# Front_right_lamp_v2.net
KiCad netlist of a schematic drawn in EAGLE
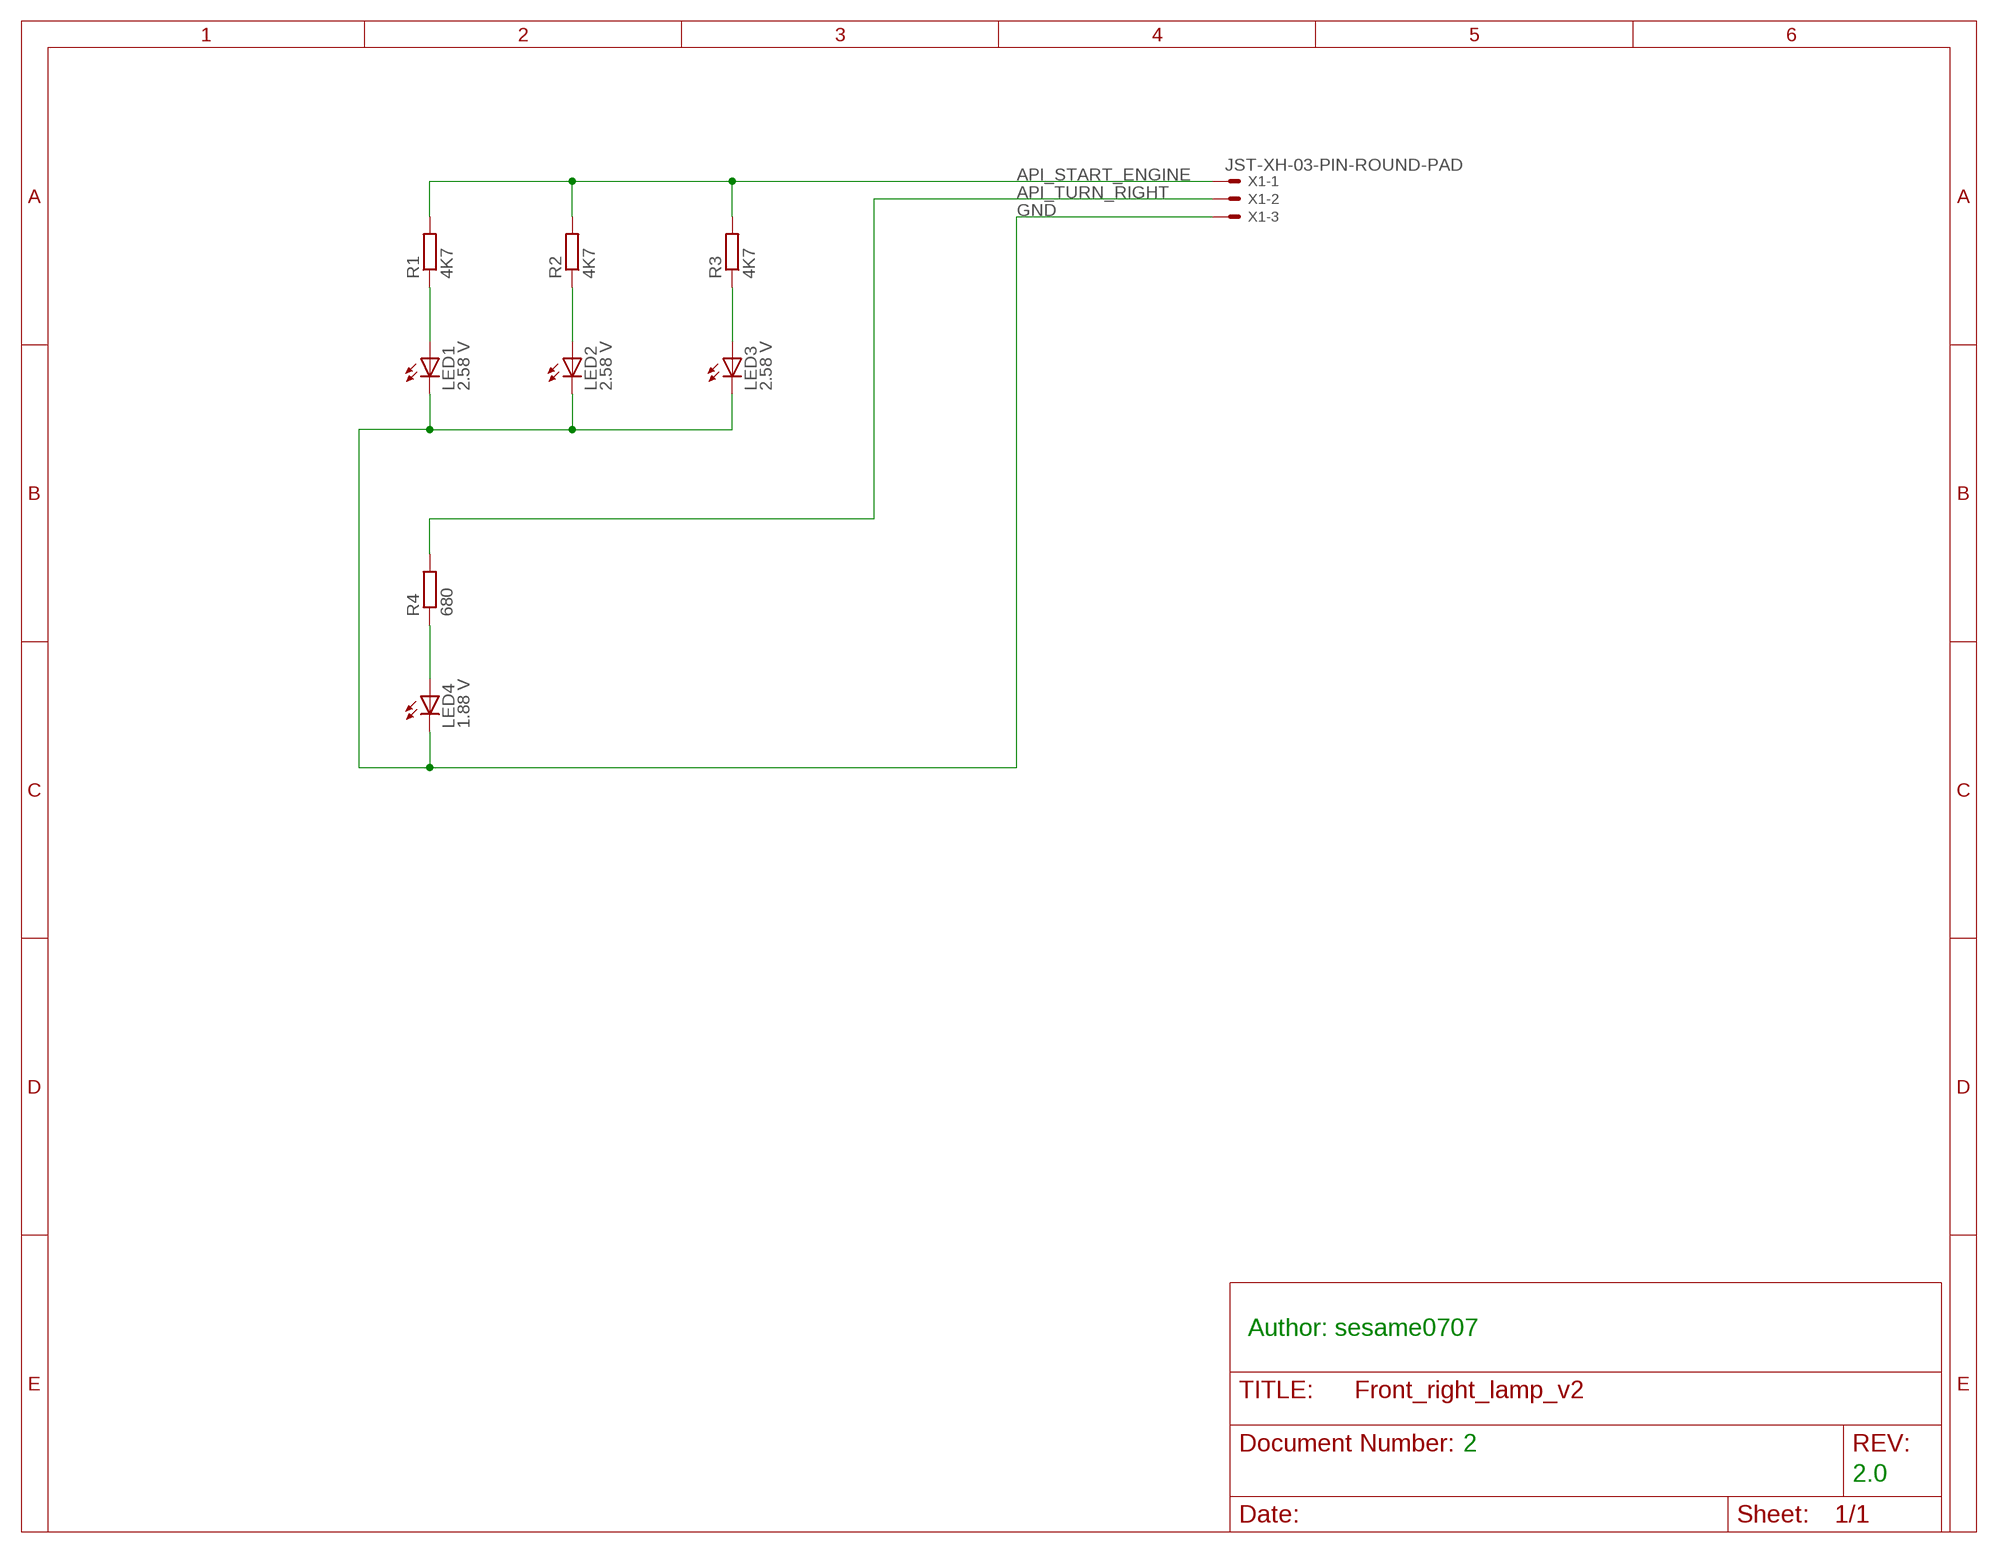
[diagram p0: schematic, sheet 1]

(export (version "E")
  (design (tool "Eeschema 10.0.6"))
  (components
    (comp (ref "LED1")
      (value "2.58 V")
      (footprint "eagle-import:LED5MM")
      (libsource (lib "eagle-import") (part "LED5MM"))
    )
    (comp (ref "LED2")
      (value "2.58 V")
      (footprint "eagle-import:LED5MM")
      (libsource (lib "eagle-import") (part "LED5MM"))
    )
    (comp (ref "LED3")
      (value "2.58 V")
      (footprint "eagle-import:LED5MM")
      (libsource (lib "eagle-import") (part "LED5MM"))
    )
    (comp (ref "LED4")
      (value "1.88 V")
      (footprint "eagle-import:LED5MM")
      (libsource (lib "eagle-import") (part "LED5MM"))
    )
    (comp (ref "R1")
      (value "4K7")
      (footprint "eagle-import:0204V")
      (libsource (lib "eagle-import") (part "R-EU_0204/2V"))
    )
    (comp (ref "R2")
      (value "4K7")
      (footprint "eagle-import:0204V")
      (libsource (lib "eagle-import") (part "R-EU_0204/2V"))
    )
    (comp (ref "R3")
      (value "4K7")
      (footprint "eagle-import:0204V")
      (libsource (lib "eagle-import") (part "R-EU_0204/2V"))
    )
    (comp (ref "R4")
      (value "680")
      (footprint "eagle-import:0204V")
      (libsource (lib "eagle-import") (part "R-EU_0204/2V"))
    )
    (comp (ref "X1")
      (value "JST-XH-03-PIN-ROUND-PAD")
      (footprint "eagle-import:JST-XH-03-PACKAGE-ROUND-PAD")
      (libsource (lib "eagle-import") (part "JST-XH-03-PIN-ROUND-PAD"))
    )
  )
  (nets
    (net (code "1") (name "/API_START_ENGINE") (class "Default")
      (node (ref "R1") (pin "2") (pinfunction "2_2") (pintype "passive"))
      (node (ref "R2") (pin "2") (pinfunction "2_2") (pintype "passive"))
      (node (ref "R3") (pin "2") (pinfunction "2_2") (pintype "passive"))
      (node (ref "X1") (pin "1") (pinfunction "S_1") (pintype "passive"))
    )
    (net (code "2") (name "/API_TURN_RIGHT") (class "Default")
      (node (ref "R4") (pin "2") (pinfunction "2_2") (pintype "passive"))
      (node (ref "X1") (pin "2") (pinfunction "S_2") (pintype "passive"))
    )
    (net (code "3") (name "/GND") (class "Default")
      (node (ref "LED1") (pin "K") (pinfunction "C_K") (pintype "passive"))
      (node (ref "LED2") (pin "K") (pinfunction "C_K") (pintype "passive"))
      (node (ref "LED3") (pin "K") (pinfunction "C_K") (pintype "passive"))
      (node (ref "LED4") (pin "K") (pinfunction "C_K") (pintype "passive"))
      (node (ref "X1") (pin "3") (pinfunction "S_3") (pintype "passive"))
    )
    (net (code "4") (name "Net-(LED1-PadA)") (class "Default")
      (node (ref "LED1") (pin "A") (pinfunction "A_A") (pintype "passive"))
      (node (ref "R1") (pin "1") (pinfunction "1_1") (pintype "passive"))
    )
    (net (code "5") (name "Net-(LED2-PadA)") (class "Default")
      (node (ref "LED2") (pin "A") (pinfunction "A_A") (pintype "passive"))
      (node (ref "R2") (pin "1") (pinfunction "1_1") (pintype "passive"))
    )
    (net (code "6") (name "Net-(LED3-PadA)") (class "Default")
      (node (ref "LED3") (pin "A") (pinfunction "A_A") (pintype "passive"))
      (node (ref "R3") (pin "1") (pinfunction "1_1") (pintype "passive"))
    )
    (net (code "7") (name "Net-(LED4-PadA)") (class "Default")
      (node (ref "LED4") (pin "A") (pinfunction "A_A") (pintype "passive"))
      (node (ref "R4") (pin "1") (pinfunction "1_1") (pintype "passive"))
    )
  )
)
